# TCS531000_ROM-el_v1.net
KiCad netlist of a schematic drawn in EAGLE
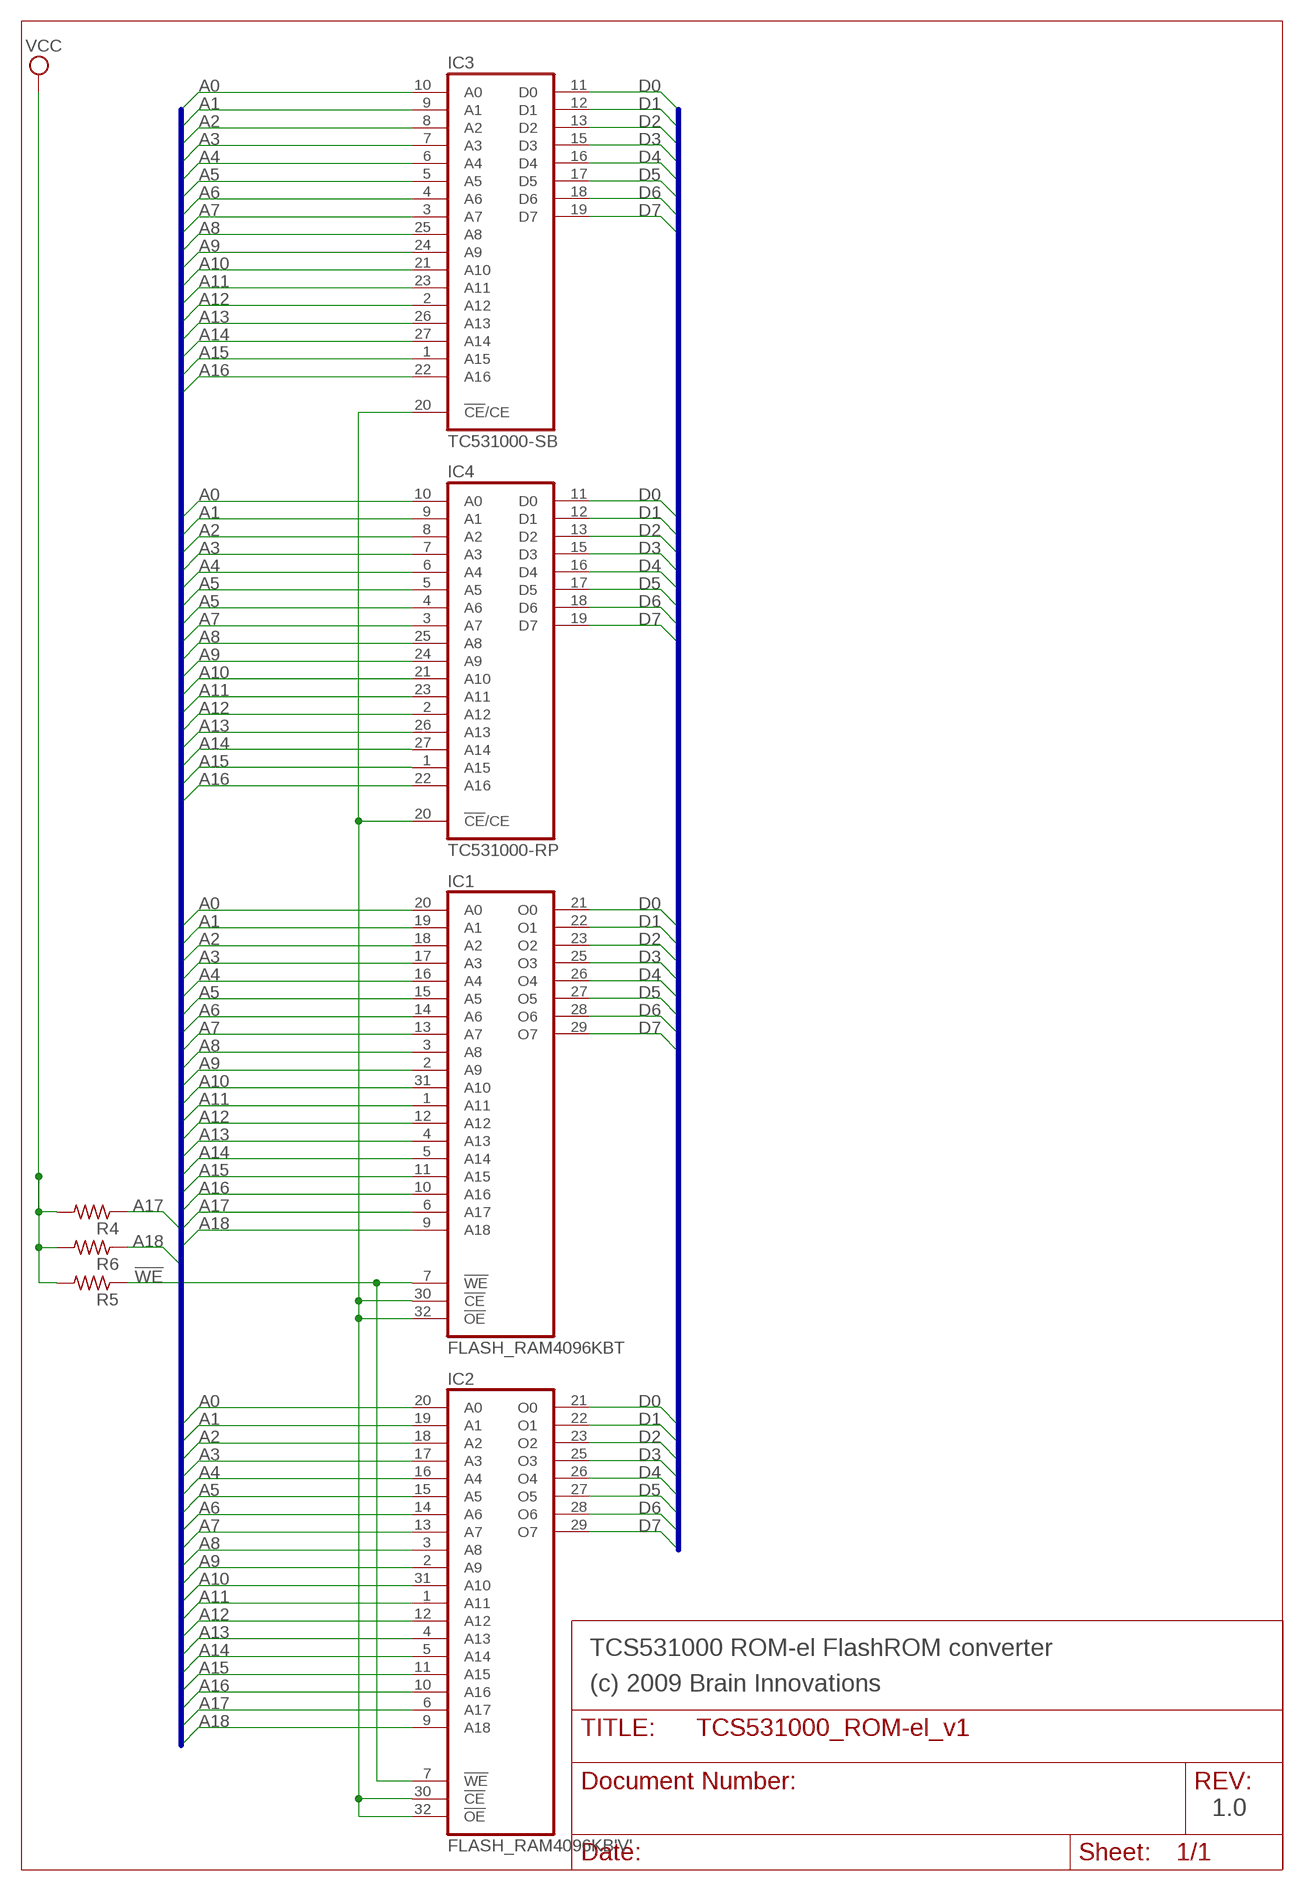
[diagram p0: schematic, sheet 1]

(export (version "E")
  (design (tool "Eeschema 10.0.6"))
  (components
    (comp (ref "IC1")
      (value "FLASH_RAM4096KBT")
      (footprint "eagle-import:TSOP32")
      (libsource (lib "eagle-import") (part "FLASH_RAM4096KB'T'"))
    )
    (comp (ref "IC2")
      (value "FLASH_RAM4096KB'V'")
      (footprint "eagle-import:VSOP32")
      (libsource (lib "eagle-import") (part "FLASH_RAM4096KB'V'"))
    )
    (comp (ref "IC3")
      (value "TC531000-SB")
      (footprint "eagle-import:DIL28-SMD-REVERSE")
      (libsource (lib "eagle-import") (part "TC531000-SB"))
    )
    (comp (ref "IC4")
      (value "TC531000-RP")
      (footprint "eagle-import:DIL28-ROUNDPAD")
      (libsource (lib "eagle-import") (part "TC531000-RP"))
    )
    (comp (ref "R4")
      (value "R-US_R0805")
      (footprint "eagle-import:R0805")
      (libsource (lib "eagle-import") (part "R-US_R0805"))
    )
    (comp (ref "R5")
      (value "R-US_R0805")
      (footprint "eagle-import:R0805")
      (libsource (lib "eagle-import") (part "R-US_R0805"))
    )
    (comp (ref "R6")
      (value "R-US_R0805")
      (footprint "eagle-import:R0805")
      (libsource (lib "eagle-import") (part "R-US_R0805"))
    )
  )
  (nets
    (net (code "1") (name "/A0") (class "Default")
      (node (ref "IC1") (pin "20") (pinfunction "A0_20") (pintype "input"))
      (node (ref "IC2") (pin "20") (pinfunction "A0_20") (pintype "input"))
      (node (ref "IC3") (pin "10") (pinfunction "A0_10") (pintype "input"))
      (node (ref "IC4") (pin "10") (pinfunction "A0_10") (pintype "input"))
    )
    (net (code "2") (name "/A1") (class "Default")
      (node (ref "IC1") (pin "19") (pinfunction "A1_19") (pintype "input"))
      (node (ref "IC2") (pin "19") (pinfunction "A1_19") (pintype "input"))
      (node (ref "IC3") (pin "9") (pinfunction "A1_9") (pintype "input"))
      (node (ref "IC4") (pin "9") (pinfunction "A1_9") (pintype "input"))
    )
    (net (code "3") (name "/A2") (class "Default")
      (node (ref "IC1") (pin "18") (pinfunction "A2_18") (pintype "input"))
      (node (ref "IC2") (pin "18") (pinfunction "A2_18") (pintype "input"))
      (node (ref "IC3") (pin "8") (pinfunction "A2_8") (pintype "input"))
      (node (ref "IC4") (pin "8") (pinfunction "A2_8") (pintype "input"))
    )
    (net (code "4") (name "/A3") (class "Default")
      (node (ref "IC1") (pin "17") (pinfunction "A3_17") (pintype "input"))
      (node (ref "IC2") (pin "17") (pinfunction "A3_17") (pintype "input"))
      (node (ref "IC3") (pin "7") (pinfunction "A3_7") (pintype "input"))
      (node (ref "IC4") (pin "7") (pinfunction "A3_7") (pintype "input"))
    )
    (net (code "5") (name "/A4") (class "Default")
      (node (ref "IC1") (pin "16") (pinfunction "A4_16") (pintype "input"))
      (node (ref "IC2") (pin "16") (pinfunction "A4_16") (pintype "input"))
      (node (ref "IC3") (pin "6") (pinfunction "A4_6") (pintype "input"))
      (node (ref "IC4") (pin "6") (pinfunction "A4_6") (pintype "input"))
    )
    (net (code "6") (name "/A5") (class "Default")
      (node (ref "IC1") (pin "15") (pinfunction "A5_15") (pintype "input"))
      (node (ref "IC2") (pin "15") (pinfunction "A5_15") (pintype "input"))
      (node (ref "IC3") (pin "5") (pinfunction "A5_5") (pintype "input"))
      (node (ref "IC4") (pin "5") (pinfunction "A5_5") (pintype "input"))
    )
    (net (code "7") (name "/A6") (class "Default")
      (node (ref "IC1") (pin "14") (pinfunction "A6_14") (pintype "input"))
      (node (ref "IC2") (pin "14") (pinfunction "A6_14") (pintype "input"))
      (node (ref "IC3") (pin "4") (pinfunction "A6_4") (pintype "input"))
      (node (ref "IC4") (pin "4") (pinfunction "A6_4") (pintype "input"))
    )
    (net (code "8") (name "/A7") (class "Default")
      (node (ref "IC1") (pin "13") (pinfunction "A7_13") (pintype "input"))
      (node (ref "IC2") (pin "13") (pinfunction "A7_13") (pintype "input"))
      (node (ref "IC3") (pin "3") (pinfunction "A7_3") (pintype "input"))
      (node (ref "IC4") (pin "3") (pinfunction "A7_3") (pintype "input"))
    )
    (net (code "9") (name "/A8") (class "Default")
      (node (ref "IC1") (pin "3") (pinfunction "A8_3") (pintype "input"))
      (node (ref "IC2") (pin "3") (pinfunction "A8_3") (pintype "input"))
      (node (ref "IC3") (pin "25") (pinfunction "A8_25") (pintype "input"))
      (node (ref "IC4") (pin "25") (pinfunction "A8_25") (pintype "input"))
    )
    (net (code "10") (name "/A9") (class "Default")
      (node (ref "IC1") (pin "2") (pinfunction "A9_2") (pintype "input"))
      (node (ref "IC2") (pin "2") (pinfunction "A9_2") (pintype "input"))
      (node (ref "IC3") (pin "24") (pinfunction "A9_24") (pintype "input"))
      (node (ref "IC4") (pin "24") (pinfunction "A9_24") (pintype "input"))
    )
    (net (code "11") (name "/A10") (class "Default")
      (node (ref "IC1") (pin "31") (pinfunction "A10_31") (pintype "input"))
      (node (ref "IC2") (pin "31") (pinfunction "A10_31") (pintype "input"))
      (node (ref "IC3") (pin "21") (pinfunction "A10_21") (pintype "input"))
      (node (ref "IC4") (pin "21") (pinfunction "A10_21") (pintype "input"))
    )
    (net (code "12") (name "/A11") (class "Default")
      (node (ref "IC1") (pin "1") (pinfunction "A11_1") (pintype "input"))
      (node (ref "IC2") (pin "1") (pinfunction "A11_1") (pintype "input"))
      (node (ref "IC3") (pin "23") (pinfunction "A11_23") (pintype "input"))
      (node (ref "IC4") (pin "23") (pinfunction "A11_23") (pintype "input"))
    )
    (net (code "13") (name "/A12") (class "Default")
      (node (ref "IC1") (pin "12") (pinfunction "A12_12") (pintype "input"))
      (node (ref "IC2") (pin "12") (pinfunction "A12_12") (pintype "input"))
      (node (ref "IC3") (pin "2") (pinfunction "A12_2") (pintype "input"))
      (node (ref "IC4") (pin "2") (pinfunction "A12_2") (pintype "input"))
    )
    (net (code "14") (name "/A13") (class "Default")
      (node (ref "IC1") (pin "4") (pinfunction "A13_4") (pintype "input"))
      (node (ref "IC2") (pin "4") (pinfunction "A13_4") (pintype "input"))
      (node (ref "IC3") (pin "26") (pinfunction "A13_26") (pintype "input"))
      (node (ref "IC4") (pin "26") (pinfunction "A13_26") (pintype "input"))
    )
    (net (code "15") (name "/A14") (class "Default")
      (node (ref "IC1") (pin "5") (pinfunction "A14_5") (pintype "input"))
      (node (ref "IC2") (pin "5") (pinfunction "A14_5") (pintype "input"))
      (node (ref "IC3") (pin "27") (pinfunction "A14_27") (pintype "input"))
      (node (ref "IC4") (pin "27") (pinfunction "A14_27") (pintype "input"))
    )
    (net (code "16") (name "/A15") (class "Default")
      (node (ref "IC1") (pin "11") (pinfunction "A15_11") (pintype "input"))
      (node (ref "IC2") (pin "11") (pinfunction "A15_11") (pintype "input"))
      (node (ref "IC3") (pin "1") (pinfunction "A15_1") (pintype "input"))
      (node (ref "IC4") (pin "1") (pinfunction "A15_1") (pintype "input"))
    )
    (net (code "17") (name "/A16") (class "Default")
      (node (ref "IC1") (pin "10") (pinfunction "A16_10") (pintype "input"))
      (node (ref "IC2") (pin "10") (pinfunction "A16_10") (pintype "input"))
      (node (ref "IC3") (pin "22") (pinfunction "A16_22") (pintype "input"))
      (node (ref "IC4") (pin "22") (pinfunction "A16_22") (pintype "input"))
    )
    (net (code "18") (name "/A17") (class "Default")
      (node (ref "IC1") (pin "6") (pinfunction "A17_6") (pintype "input"))
      (node (ref "IC2") (pin "6") (pinfunction "A17_6") (pintype "input"))
      (node (ref "R4") (pin "1") (pinfunction "1_1") (pintype "passive"))
    )
    (net (code "19") (name "/A18") (class "Default")
      (node (ref "IC1") (pin "9") (pinfunction "A18_9") (pintype "input"))
      (node (ref "IC2") (pin "9") (pinfunction "A18_9") (pintype "input"))
      (node (ref "R6") (pin "1") (pinfunction "1_1") (pintype "passive"))
    )
    (net (code "20") (name "/D0") (class "Default")
      (node (ref "IC1") (pin "21") (pinfunction "O0_21") (pintype "tri_state"))
      (node (ref "IC2") (pin "21") (pinfunction "O0_21") (pintype "tri_state"))
      (node (ref "IC3") (pin "11") (pinfunction "D0_11") (pintype "tri_state"))
      (node (ref "IC4") (pin "11") (pinfunction "D0_11") (pintype "tri_state"))
    )
    (net (code "21") (name "/D1") (class "Default")
      (node (ref "IC1") (pin "22") (pinfunction "O1_22") (pintype "tri_state"))
      (node (ref "IC2") (pin "22") (pinfunction "O1_22") (pintype "tri_state"))
      (node (ref "IC3") (pin "12") (pinfunction "D1_12") (pintype "tri_state"))
      (node (ref "IC4") (pin "12") (pinfunction "D1_12") (pintype "tri_state"))
    )
    (net (code "22") (name "/D2") (class "Default")
      (node (ref "IC1") (pin "23") (pinfunction "O2_23") (pintype "tri_state"))
      (node (ref "IC2") (pin "23") (pinfunction "O2_23") (pintype "tri_state"))
      (node (ref "IC3") (pin "13") (pinfunction "D2_13") (pintype "tri_state"))
      (node (ref "IC4") (pin "13") (pinfunction "D2_13") (pintype "tri_state"))
    )
    (net (code "23") (name "/D3") (class "Default")
      (node (ref "IC1") (pin "25") (pinfunction "O3_25") (pintype "tri_state"))
      (node (ref "IC2") (pin "25") (pinfunction "O3_25") (pintype "tri_state"))
      (node (ref "IC3") (pin "15") (pinfunction "D3_15") (pintype "tri_state"))
      (node (ref "IC4") (pin "15") (pinfunction "D3_15") (pintype "tri_state"))
    )
    (net (code "24") (name "/D4") (class "Default")
      (node (ref "IC1") (pin "26") (pinfunction "O4_26") (pintype "tri_state"))
      (node (ref "IC2") (pin "26") (pinfunction "O4_26") (pintype "tri_state"))
      (node (ref "IC3") (pin "16") (pinfunction "D4_16") (pintype "tri_state"))
      (node (ref "IC4") (pin "16") (pinfunction "D4_16") (pintype "tri_state"))
    )
    (net (code "25") (name "/D5") (class "Default")
      (node (ref "IC1") (pin "27") (pinfunction "O5_27") (pintype "tri_state"))
      (node (ref "IC2") (pin "27") (pinfunction "O5_27") (pintype "tri_state"))
      (node (ref "IC3") (pin "17") (pinfunction "D5_17") (pintype "tri_state"))
      (node (ref "IC4") (pin "17") (pinfunction "D5_17") (pintype "tri_state"))
    )
    (net (code "26") (name "/D6") (class "Default")
      (node (ref "IC1") (pin "28") (pinfunction "O6_28") (pintype "tri_state"))
      (node (ref "IC2") (pin "28") (pinfunction "O6_28") (pintype "tri_state"))
      (node (ref "IC3") (pin "18") (pinfunction "D6_18") (pintype "tri_state"))
      (node (ref "IC4") (pin "18") (pinfunction "D6_18") (pintype "tri_state"))
    )
    (net (code "27") (name "/D7") (class "Default")
      (node (ref "IC1") (pin "29") (pinfunction "O7_29") (pintype "tri_state"))
      (node (ref "IC2") (pin "29") (pinfunction "O7_29") (pintype "tri_state"))
      (node (ref "IC3") (pin "19") (pinfunction "D7_19") (pintype "tri_state"))
      (node (ref "IC4") (pin "19") (pinfunction "D7_19") (pintype "tri_state"))
    )
    (net (code "28") (name "/~{WE}") (class "Default")
      (node (ref "IC1") (pin "7") (pinfunction "~{WE}_7") (pintype "input"))
      (node (ref "IC2") (pin "7") (pinfunction "~{WE}_7") (pintype "input"))
      (node (ref "R5") (pin "1") (pinfunction "1_1") (pintype "passive"))
    )
    (net (code "29") (name "Net-(IC1A-~{CE})") (class "Default")
      (node (ref "IC1") (pin "30") (pinfunction "~{CE}_30") (pintype "input"))
      (node (ref "IC1") (pin "32") (pinfunction "~{OE}_32") (pintype "input"))
      (node (ref "IC2") (pin "30") (pinfunction "~{CE}_30") (pintype "input"))
      (node (ref "IC2") (pin "32") (pinfunction "~{OE}_32") (pintype "input"))
      (node (ref "IC3") (pin "20") (pinfunction "~{CE}/CE_20") (pintype "input"))
      (node (ref "IC4") (pin "20") (pinfunction "~{CE}/CE_20") (pintype "input"))
    )
    (net (code "30") (name "VCC") (class "Default")
      (node (ref "R4") (pin "2") (pinfunction "2_2") (pintype "passive"))
      (node (ref "R5") (pin "2") (pinfunction "2_2") (pintype "passive"))
      (node (ref "R6") (pin "2") (pinfunction "2_2") (pintype "passive"))
    )
  )
)
